# B104B.net
KiCad netlist of a schematic drawn in EAGLE
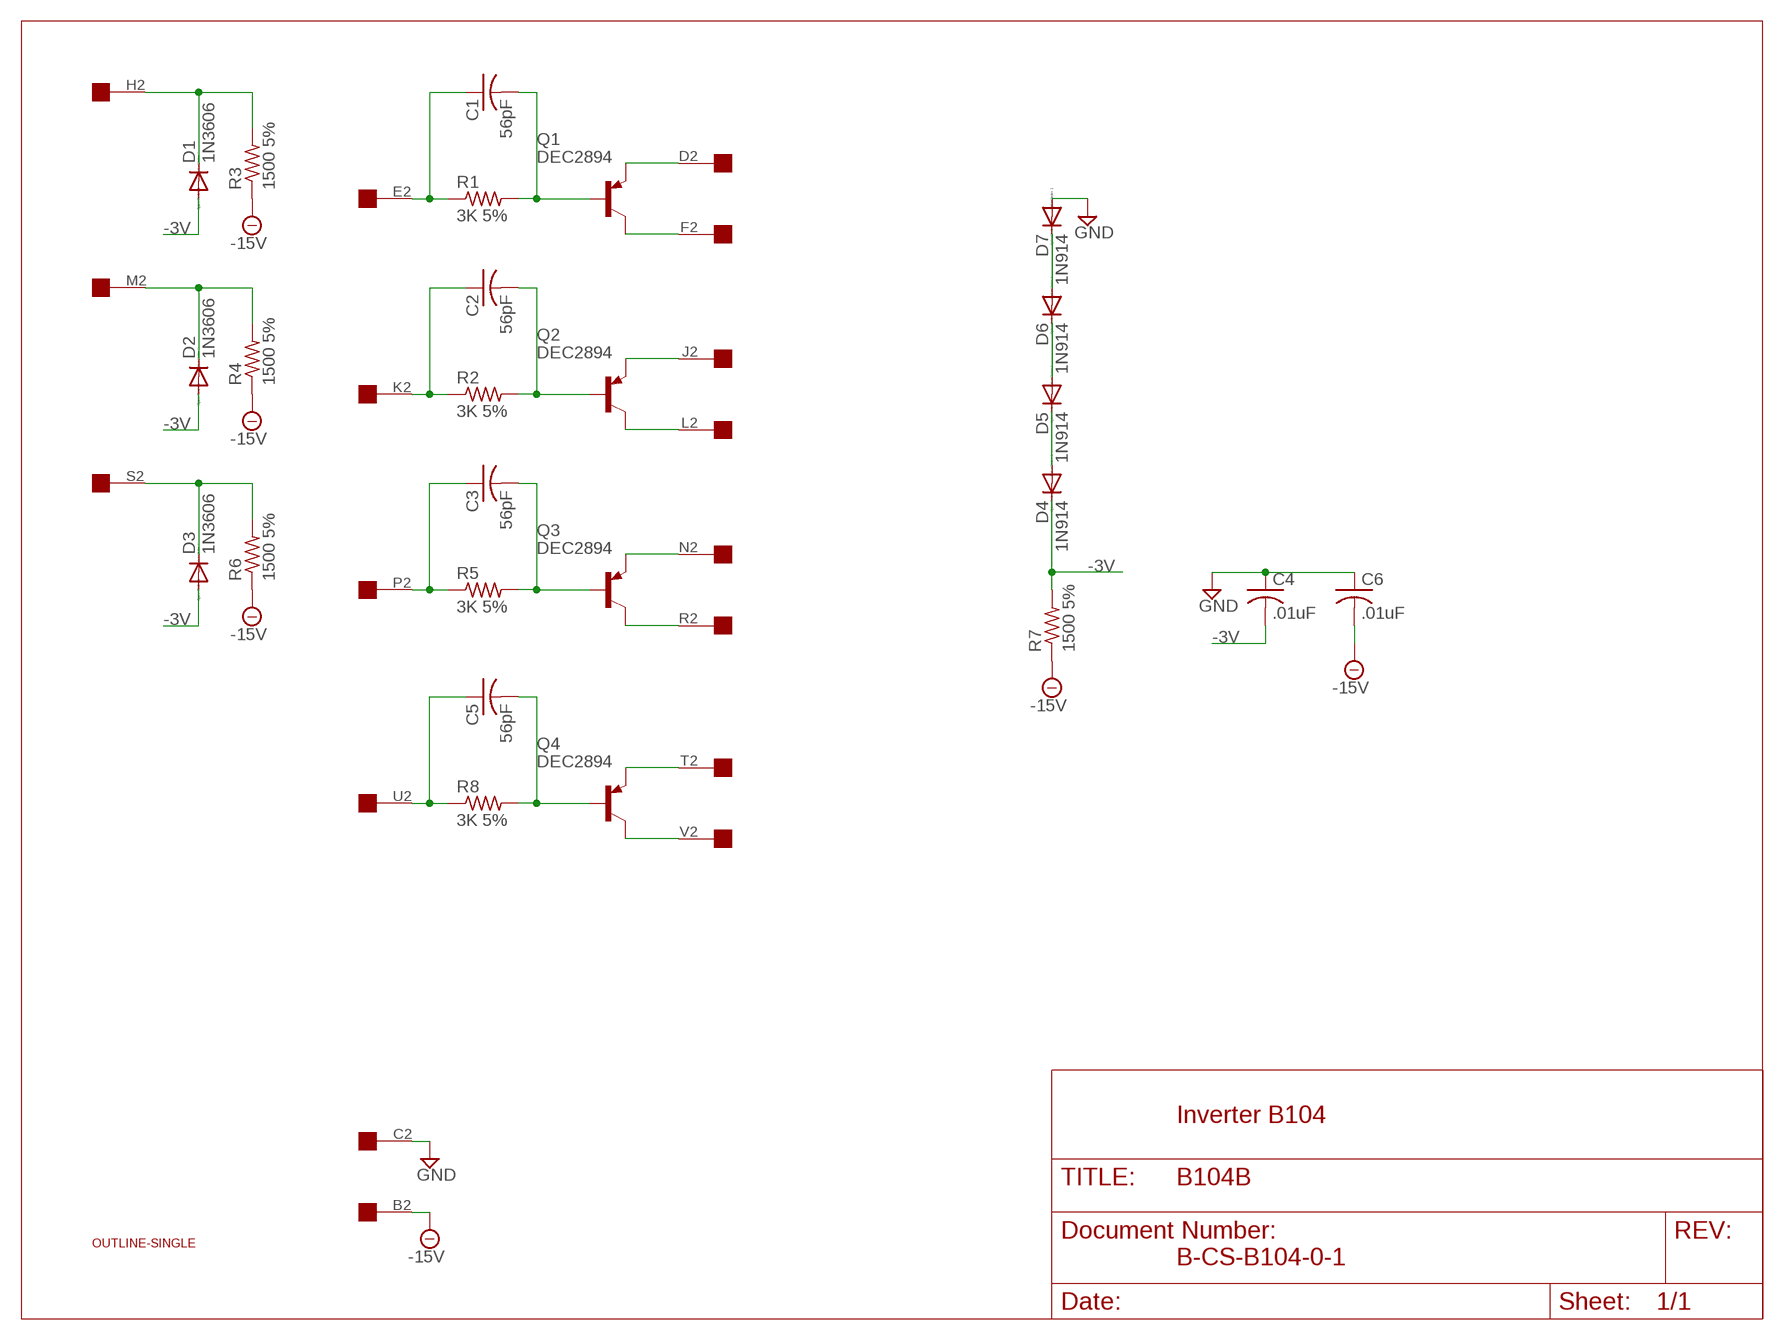
[diagram p0: schematic, sheet 1]

(export (version "E")
  (design (tool "Eeschema 10.0.6"))
  (components
    (comp (ref "C1")
      (value "56pF")
      (footprint "eagle-import:C075-032X103")
      (libsource (lib "eagle-import") (part "C-US075-032X103"))
    )
    (comp (ref "C2")
      (value "56pF")
      (footprint "eagle-import:C075-032X103")
      (libsource (lib "eagle-import") (part "C-US075-032X103"))
    )
    (comp (ref "C3")
      (value "56pF")
      (footprint "eagle-import:C075-032X103")
      (libsource (lib "eagle-import") (part "C-US075-032X103"))
    )
    (comp (ref "C4")
      (value ".01uF")
      (footprint "eagle-import:C050-025X075")
      (libsource (lib "eagle-import") (part "C-US050-025X075"))
    )
    (comp (ref "C5")
      (value "56pF")
      (footprint "eagle-import:C075-032X103")
      (libsource (lib "eagle-import") (part "C-US075-032X103"))
    )
    (comp (ref "C6")
      (value ".01uF")
      (footprint "eagle-import:C050-025X075")
      (libsource (lib "eagle-import") (part "C-US050-025X075"))
    )
    (comp (ref "D1")
      (value "1N3606")
      (footprint "eagle-import:DO35-10")
      (libsource (lib "eagle-import") (part "1N4148DO35-10"))
    )
    (comp (ref "D2")
      (value "1N3606")
      (footprint "eagle-import:DO35-10")
      (libsource (lib "eagle-import") (part "1N4148DO35-10"))
    )
    (comp (ref "D3")
      (value "1N3606")
      (footprint "eagle-import:DO35-10")
      (libsource (lib "eagle-import") (part "1N4148DO35-10"))
    )
    (comp (ref "D4")
      (value "1N914")
      (footprint "eagle-import:DO35-10")
      (libsource (lib "eagle-import") (part "1N4148DO35-10"))
    )
    (comp (ref "D5")
      (value "1N914")
      (footprint "eagle-import:DO35-10")
      (libsource (lib "eagle-import") (part "1N4148DO35-10"))
    )
    (comp (ref "D6")
      (value "1N914")
      (footprint "eagle-import:DO35-10")
      (libsource (lib "eagle-import") (part "1N4148DO35-10"))
    )
    (comp (ref "D7")
      (value "1N914")
      (footprint "eagle-import:DO35-10")
      (libsource (lib "eagle-import") (part "1N4148DO35-10"))
    )
    (comp (ref "Q1")
      (value "DEC2894")
      (footprint "eagle-import:TO39")
      (libsource (lib "eagle-import") (part "2N2904"))
    )
    (comp (ref "Q2")
      (value "DEC2894")
      (footprint "eagle-import:TO39")
      (libsource (lib "eagle-import") (part "2N2904"))
    )
    (comp (ref "Q3")
      (value "DEC2894")
      (footprint "eagle-import:TO39")
      (libsource (lib "eagle-import") (part "2N2904"))
    )
    (comp (ref "Q4")
      (value "DEC2894")
      (footprint "eagle-import:TO39")
      (libsource (lib "eagle-import") (part "2N2904"))
    )
    (comp (ref "R1")
      (value "3K 5%")
      (footprint "eagle-import:0207_10")
      (libsource (lib "eagle-import") (part "R-US_0207/10"))
    )
    (comp (ref "R2")
      (value "3K 5%")
      (footprint "eagle-import:0207_10")
      (libsource (lib "eagle-import") (part "R-US_0207/10"))
    )
    (comp (ref "R3")
      (value "1500 5%")
      (footprint "eagle-import:0207_10")
      (libsource (lib "eagle-import") (part "R-US_0207/10"))
    )
    (comp (ref "R4")
      (value "1500 5%")
      (footprint "eagle-import:0207_10")
      (libsource (lib "eagle-import") (part "R-US_0207/10"))
    )
    (comp (ref "R5")
      (value "3K 5%")
      (footprint "eagle-import:0207_10")
      (libsource (lib "eagle-import") (part "R-US_0207/10"))
    )
    (comp (ref "R6")
      (value "1500 5%")
      (footprint "eagle-import:0207_10")
      (libsource (lib "eagle-import") (part "R-US_0207/10"))
    )
    (comp (ref "R7")
      (value "1500 5%")
      (footprint "eagle-import:0207_10")
      (libsource (lib "eagle-import") (part "R-US_0207/10"))
    )
    (comp (ref "R8")
      (value "3K 5%")
      (footprint "eagle-import:0207_10")
      (libsource (lib "eagle-import") (part "R-US_0207/10"))
    )
    (comp (ref "U$1")
      (value "OUTLINE-SINGLE")
      (footprint "eagle-import:SINGLE")
      (libsource (lib "eagle-import") (part "OUTLINE-SINGLE"))
    )
    (comp (ref "U$2")
      (value "EDGE-1")
      (footprint "eagle-import:EDGE-CON1")
      (libsource (lib "eagle-import") (part "EDGE-1"))
    )
  )
  (nets
    (net (code "1") (name "-15V") (class "Default")
      (node (ref "C6") (pin "2") (pinfunction "2_2") (pintype "passive"))
      (node (ref "R3") (pin "1") (pinfunction "1_1") (pintype "passive"))
      (node (ref "R4") (pin "1") (pinfunction "1_1") (pintype "passive"))
      (node (ref "R6") (pin "1") (pinfunction "1_1") (pintype "passive"))
      (node (ref "R7") (pin "1") (pinfunction "1_1") (pintype "passive"))
      (node (ref "U$2") (pin "B2") (pinfunction "1_B2") (pintype "bidirectional"))
    )
    (net (code "2") (name "/-3V") (class "Default")
      (node (ref "C4") (pin "2") (pinfunction "2_2") (pintype "passive"))
      (node (ref "D1") (pin "A") (pinfunction "A_A") (pintype "passive"))
      (node (ref "D2") (pin "A") (pinfunction "A_A") (pintype "passive"))
      (node (ref "D3") (pin "A") (pinfunction "A_A") (pintype "passive"))
      (node (ref "D4") (pin "C") (pinfunction "C_C") (pintype "passive"))
      (node (ref "R7") (pin "2") (pinfunction "2_2") (pintype "passive"))
    )
    (net (code "3") (name "GND") (class "Default")
      (node (ref "C4") (pin "1") (pinfunction "1_1") (pintype "passive"))
      (node (ref "C6") (pin "1") (pinfunction "1_1") (pintype "passive"))
      (node (ref "D7") (pin "A") (pinfunction "A_A") (pintype "passive"))
      (node (ref "U$2") (pin "C2") (pinfunction "1_C2") (pintype "bidirectional"))
    )
    (net (code "4") (name "Net-(D4-PadA)") (class "Default")
      (node (ref "D4") (pin "A") (pinfunction "A_A") (pintype "passive"))
      (node (ref "D5") (pin "C") (pinfunction "C_C") (pintype "passive"))
    )
    (net (code "5") (name "Net-(D5-PadA)") (class "Default")
      (node (ref "D5") (pin "A") (pinfunction "A_A") (pintype "passive"))
      (node (ref "D6") (pin "C") (pinfunction "C_C") (pintype "passive"))
    )
    (net (code "6") (name "Net-(D6-PadA)") (class "Default")
      (node (ref "D6") (pin "A") (pinfunction "A_A") (pintype "passive"))
      (node (ref "D7") (pin "C") (pinfunction "C_C") (pintype "passive"))
    )
    (net (code "7") (name "Net-(Q1-B)") (class "Default")
      (node (ref "C1") (pin "2") (pinfunction "2_2") (pintype "passive"))
      (node (ref "Q1") (pin "2") (pinfunction "B_2") (pintype "passive"))
      (node (ref "R1") (pin "2") (pinfunction "2_2") (pintype "passive"))
    )
    (net (code "8") (name "Net-(Q1-C)") (class "Default")
      (node (ref "Q1") (pin "3") (pinfunction "C_3") (pintype "passive"))
      (node (ref "U$2") (pin "F2") (pinfunction "1_F2") (pintype "bidirectional"))
    )
    (net (code "9") (name "Net-(Q1-E)") (class "Default")
      (node (ref "Q1") (pin "1") (pinfunction "E_1") (pintype "passive"))
      (node (ref "U$2") (pin "D2") (pinfunction "1_D2") (pintype "bidirectional"))
    )
    (net (code "10") (name "Net-(Q2-B)") (class "Default")
      (node (ref "C2") (pin "2") (pinfunction "2_2") (pintype "passive"))
      (node (ref "Q2") (pin "2") (pinfunction "B_2") (pintype "passive"))
      (node (ref "R2") (pin "2") (pinfunction "2_2") (pintype "passive"))
    )
    (net (code "11") (name "Net-(Q2-C)") (class "Default")
      (node (ref "Q2") (pin "3") (pinfunction "C_3") (pintype "passive"))
      (node (ref "U$2") (pin "L2") (pinfunction "1_L2") (pintype "bidirectional"))
    )
    (net (code "12") (name "Net-(Q2-E)") (class "Default")
      (node (ref "Q2") (pin "1") (pinfunction "E_1") (pintype "passive"))
      (node (ref "U$2") (pin "J2") (pinfunction "1_J2") (pintype "bidirectional"))
    )
    (net (code "13") (name "Net-(Q3-B)") (class "Default")
      (node (ref "C3") (pin "2") (pinfunction "2_2") (pintype "passive"))
      (node (ref "Q3") (pin "2") (pinfunction "B_2") (pintype "passive"))
      (node (ref "R5") (pin "2") (pinfunction "2_2") (pintype "passive"))
    )
    (net (code "14") (name "Net-(Q3-C)") (class "Default")
      (node (ref "Q3") (pin "3") (pinfunction "C_3") (pintype "passive"))
      (node (ref "U$2") (pin "R2") (pinfunction "1_R2") (pintype "bidirectional"))
    )
    (net (code "15") (name "Net-(Q3-E)") (class "Default")
      (node (ref "Q3") (pin "1") (pinfunction "E_1") (pintype "passive"))
      (node (ref "U$2") (pin "N2") (pinfunction "1_N2") (pintype "bidirectional"))
    )
    (net (code "16") (name "Net-(Q4-B)") (class "Default")
      (node (ref "C5") (pin "2") (pinfunction "2_2") (pintype "passive"))
      (node (ref "Q4") (pin "2") (pinfunction "B_2") (pintype "passive"))
      (node (ref "R8") (pin "2") (pinfunction "2_2") (pintype "passive"))
    )
    (net (code "17") (name "Net-(Q4-C)") (class "Default")
      (node (ref "Q4") (pin "3") (pinfunction "C_3") (pintype "passive"))
      (node (ref "U$2") (pin "V2") (pinfunction "1_V2") (pintype "bidirectional"))
    )
    (net (code "18") (name "Net-(Q4-E)") (class "Default")
      (node (ref "Q4") (pin "1") (pinfunction "E_1") (pintype "passive"))
      (node (ref "U$2") (pin "T2") (pinfunction "1_T2") (pintype "bidirectional"))
    )
    (net (code "19") (name "Net-(U$2E-1)") (class "Default")
      (node (ref "C1") (pin "1") (pinfunction "1_1") (pintype "passive"))
      (node (ref "R1") (pin "1") (pinfunction "1_1") (pintype "passive"))
      (node (ref "U$2") (pin "E2") (pinfunction "1_E2") (pintype "bidirectional"))
    )
    (net (code "20") (name "Net-(U$2G-1)") (class "Default")
      (node (ref "D1") (pin "C") (pinfunction "C_C") (pintype "passive"))
      (node (ref "R3") (pin "2") (pinfunction "2_2") (pintype "passive"))
      (node (ref "U$2") (pin "H2") (pinfunction "1_H2") (pintype "bidirectional"))
    )
    (net (code "21") (name "Net-(U$2I-1)") (class "Default")
      (node (ref "C2") (pin "1") (pinfunction "1_1") (pintype "passive"))
      (node (ref "R2") (pin "1") (pinfunction "1_1") (pintype "passive"))
      (node (ref "U$2") (pin "K2") (pinfunction "1_K2") (pintype "bidirectional"))
    )
    (net (code "22") (name "Net-(U$2K-1)") (class "Default")
      (node (ref "D2") (pin "C") (pinfunction "C_C") (pintype "passive"))
      (node (ref "R4") (pin "2") (pinfunction "2_2") (pintype "passive"))
      (node (ref "U$2") (pin "M2") (pinfunction "1_M2") (pintype "bidirectional"))
    )
    (net (code "23") (name "Net-(U$2M-1)") (class "Default")
      (node (ref "C3") (pin "1") (pinfunction "1_1") (pintype "passive"))
      (node (ref "R5") (pin "1") (pinfunction "1_1") (pintype "passive"))
      (node (ref "U$2") (pin "P2") (pinfunction "1_P2") (pintype "bidirectional"))
    )
    (net (code "24") (name "Net-(U$2O-1)") (class "Default")
      (node (ref "D3") (pin "C") (pinfunction "C_C") (pintype "passive"))
      (node (ref "R6") (pin "2") (pinfunction "2_2") (pintype "passive"))
      (node (ref "U$2") (pin "S2") (pinfunction "1_S2") (pintype "bidirectional"))
    )
    (net (code "25") (name "Net-(U$2Q-1)") (class "Default")
      (node (ref "C5") (pin "1") (pinfunction "1_1") (pintype "passive"))
      (node (ref "R8") (pin "1") (pinfunction "1_1") (pintype "passive"))
      (node (ref "U$2") (pin "U2") (pinfunction "1_U2") (pintype "bidirectional"))
    )
  )
)
